# PH.net
KiCad netlist of a schematic drawn in Altium Designer
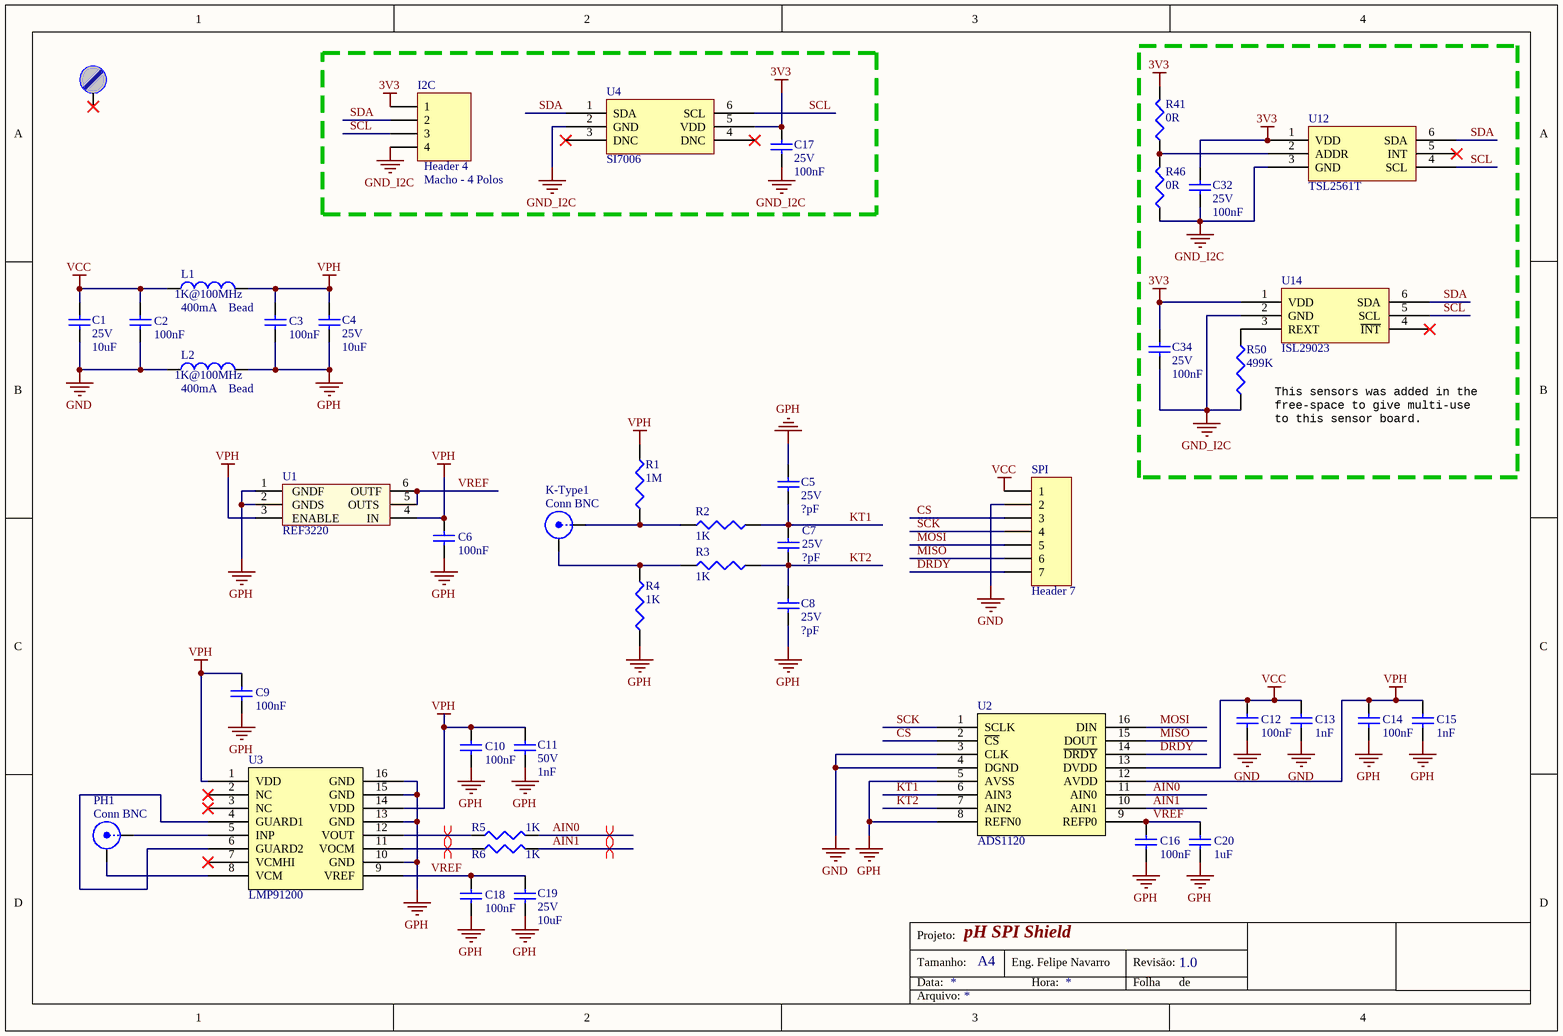
[diagram p0: PH.SchDoc]

(export (version "E")
  (design (tool "Eeschema 10.0.6"))
  (components
    (comp (ref "C1")
      (value "10uF")
      (footprint "CC0805")
      (description "Capacitor (Semiconductor SIM Model)")
      (fields (field (name "TENSÃO") "25V") (field (name "Comment") "Capacitor Cerâmico"))
      (libsource (lib "NavarroCAP") (part "Cap 10uF 25V 0805 X5R"))
    )
    (comp (ref "C2")
      (value "100nF")
      (footprint "CC0603")
      (description "Capacitor (Semiconductor SIM Model)")
      (fields (field (name "Comment") "Capacitor Cerâmico"))
      (libsource (lib "NavarroCAP") (part "Cap 100nF 25V 0603 X7R"))
    )
    (comp (ref "C3")
      (value "100nF")
      (footprint "CC0603")
      (description "Capacitor (Semiconductor SIM Model)")
      (fields (field (name "Comment") "Capacitor Cerâmico"))
      (libsource (lib "NavarroCAP") (part "Cap 100nF 25V 0603 X7R"))
    )
    (comp (ref "C4")
      (value "10uF")
      (footprint "CC0805")
      (description "Capacitor (Semiconductor SIM Model)")
      (fields (field (name "TENSÃO") "25V") (field (name "Comment") "Capacitor Cerâmico"))
      (libsource (lib "NavarroCAP") (part "Cap 10uF 25V 0805 X5R"))
    )
    (comp (ref "C5")
      (value "?pF")
      (footprint "CC0603")
      (description "Capacitor (Semiconductor SIM Model)")
      (fields (field (name "TENSÃO") "25V") (field (name "Comment") "Capacitor Cerâmico"))
      (libsource (lib "NavarroCAP") (part "Cap - $Val $V $Footprint $Classe_1"))
    )
    (comp (ref "C6")
      (value "100nF")
      (footprint "CC0603")
      (description "Capacitor (Semiconductor SIM Model)")
      (fields (field (name "Comment") "Capacitor Cerâmico"))
      (libsource (lib "NavarroCAP") (part "Cap 100nF 25V 0603 X7R"))
    )
    (comp (ref "C7")
      (value "?pF")
      (footprint "CC0603")
      (description "Capacitor (Semiconductor SIM Model)")
      (fields (field (name "TENSÃO") "25V") (field (name "Comment") "Capacitor Cerâmico"))
      (libsource (lib "NavarroCAP") (part "Cap - $Val $V $Footprint $Classe_1"))
    )
    (comp (ref "C8")
      (value "?pF")
      (footprint "CC0603")
      (description "Capacitor (Semiconductor SIM Model)")
      (fields (field (name "TENSÃO") "25V") (field (name "Comment") "Capacitor Cerâmico"))
      (libsource (lib "NavarroCAP") (part "Cap - $Val $V $Footprint $Classe_1"))
    )
    (comp (ref "C9")
      (value "100nF")
      (footprint "CC0603")
      (description "Capacitor (Semiconductor SIM Model)")
      (fields (field (name "Comment") "Capacitor Cerâmico"))
      (libsource (lib "NavarroCAP") (part "Cap 100nF 25V 0603 X7R"))
    )
    (comp (ref "C10")
      (value "100nF")
      (footprint "CC0603")
      (description "Capacitor (Semiconductor SIM Model)")
      (fields (field (name "Comment") "Capacitor Cerâmico"))
      (libsource (lib "NavarroCAP") (part "Cap 100nF 25V 0603 X7R"))
    )
    (comp (ref "C11")
      (value "1nF")
      (footprint "CC0603")
      (description "Capacitor (Semiconductor SIM Model)")
      (fields (field (name "TENSÃO") "50V") (field (name "Comment") "Capacitor Cerâmico"))
      (libsource (lib "NavarroCAP") (part "Cap 1nF 50V 0603 NP0"))
    )
    (comp (ref "C12")
      (value "100nF")
      (footprint "CC0603")
      (description "Capacitor (Semiconductor SIM Model)")
      (fields (field (name "Comment") "Capacitor Cerâmico"))
      (libsource (lib "NavarroCAP") (part "Cap 100nF 25V 0603 X7R"))
    )
    (comp (ref "C13")
      (value "1nF")
      (footprint "CC0603")
      (description "Capacitor (Semiconductor SIM Model)")
      (fields (field (name "Comment") "Capacitor Cerâmico"))
      (libsource (lib "NavarroCAP") (part "Cap 100nF 25V 0603 X7R"))
    )
    (comp (ref "C14")
      (value "100nF")
      (footprint "CC0603")
      (description "Capacitor (Semiconductor SIM Model)")
      (fields (field (name "Comment") "Capacitor Cerâmico"))
      (libsource (lib "NavarroCAP") (part "Cap 100nF 25V 0603 X7R"))
    )
    (comp (ref "C15")
      (value "1nF")
      (footprint "CC0603")
      (description "Capacitor (Semiconductor SIM Model)")
      (fields (field (name "Comment") "Capacitor Cerâmico"))
      (libsource (lib "NavarroCAP") (part "Cap 100nF 25V 0603 X7R"))
    )
    (comp (ref "C16")
      (value "100nF")
      (footprint "CC0603")
      (description "Capacitor (Semiconductor SIM Model)")
      (fields (field (name "Comment") "Capacitor Cerâmico"))
      (libsource (lib "NavarroCAP") (part "Cap 100nF 25V 0603 X7R"))
    )
    (comp (ref "C17")
      (value "100nF")
      (footprint "CC0603")
      (description "Capacitor (Semiconductor SIM Model)")
      (fields (field (name "TENSÃO") "25V") (field (name "Comment") "Capacitor Cerâmico"))
      (libsource (lib "NavarroCAP") (part "Cap 100nF 25V 0603 X7R"))
    )
    (comp (ref "C18")
      (value "100nF")
      (footprint "CC0603")
      (description "Capacitor (Semiconductor SIM Model)")
      (fields (field (name "Comment") "Capacitor Cerâmico"))
      (libsource (lib "NavarroCAP") (part "Cap 100nF 25V 0603 X7R"))
    )
    (comp (ref "C19")
      (value "10uF")
      (footprint "CC0805")
      (description "Capacitor (Semiconductor SIM Model)")
      (fields (field (name "TENSÃO") "25V") (field (name "Comment") "Capacitor Cerâmico"))
      (libsource (lib "NavarroCAP") (part "Cap 10uF 25V 0805 X5R"))
    )
    (comp (ref "C20")
      (value "1uF")
      (footprint "CC0603")
      (description "Capacitor (Semiconductor SIM Model)")
      (fields (field (name "Comment") "Capacitor Cerâmico"))
      (libsource (lib "NavarroCAP") (part "Cap 100nF 25V 0603 X7R"))
    )
    (comp (ref "C32")
      (value "100nF")
      (footprint "CC0603")
      (description "Capacitor (Semiconductor SIM Model)")
      (fields (field (name "TENSÃO") "25V") (field (name "Comment") "Capacitor Cerâmico"))
      (libsource (lib "NavarroCAP") (part "Cap 100nF 25V 0603 X7R"))
    )
    (comp (ref "C34")
      (value "100nF")
      (footprint "CC0603")
      (description "Capacitor (Semiconductor SIM Model)")
      (fields (field (name "TENSÃO") "25V") (field (name "Comment") "Capacitor Cerâmico"))
      (libsource (lib "NavarroCAP") (part "Cap 100nF 25V 0603 X7R"))
    )
    (comp (ref "I2C")
      (value "Header 4")
      (footprint "CONN HDR1X4")
      (description "Header, 4-Pin")
      (fields (field (name "ALTIUM_VALUE") "Macho - 4 Polos"))
      (libsource (lib "NavarroCON") (part "Header 4"))
    )
    (comp (ref "K-Type1")
      (value "Conn BNC")
      (footprint "CONN BNC-JACK")
      (description "Conector BNC")
      (libsource (lib "NavarroCON") (part "Conn BNC"))
    )
    (comp (ref "L1")
      (value "Bead")
      (footprint "CC0603")
      (fields (field (name "CORRENTE") "400mA") (field (name "ALTIUM_VALUE") "1K@100MHz"))
      (libsource (lib "NavarroIND") (part "Bd 1K@100MHz 0603 400mA"))
    )
    (comp (ref "L2")
      (value "Bead")
      (footprint "CC0603")
      (fields (field (name "CORRENTE") "400mA") (field (name "ALTIUM_VALUE") "1K@100MHz"))
      (libsource (lib "NavarroIND") (part "Bd 1K@100MHz 0603 400mA"))
    )
    (comp (ref "M2")
      (value "Furo de Fixação")
      (footprint "Furo_M3")
      (description "Furo para parafuso")
      (libsource (lib "Tecnoclade") (part "Parafuso"))
    )
    (comp (ref "PH1")
      (value "Conn BNC")
      (footprint "CONN BNC-JACK")
      (description "Conector BNC")
      (libsource (lib "NavarroCON") (part "Conn BNC"))
    )
    (comp (ref "R1")
      (value "1M")
      (footprint "CC0603")
      (description "Resistor")
      (libsource (lib "NavarroRES") (part "Res - $Val $% $Footprint $Pot"))
    )
    (comp (ref "R2")
      (value "1K")
      (footprint "CC0603")
      (description "Resistor")
      (libsource (lib "NavarroRES") (part "Res - $Val $% $Footprint $Pot"))
    )
    (comp (ref "R3")
      (value "1K")
      (footprint "CC0603")
      (description "Resistor")
      (libsource (lib "NavarroRES") (part "Res - $Val $% $Footprint $Pot"))
    )
    (comp (ref "R4")
      (value "1K")
      (footprint "CC0603")
      (description "Resistor")
      (libsource (lib "NavarroRES") (part "Res - $Val $% $Footprint $Pot"))
    )
    (comp (ref "R5")
      (value "1K")
      (footprint "CC0603")
      (description "Resistor")
      (libsource (lib "NavarroRES") (part "Res 1K 1% 0603 1/10W"))
    )
    (comp (ref "R6")
      (value "1K")
      (footprint "CC0603")
      (description "Resistor")
      (libsource (lib "NavarroRES") (part "Res 1K 1% 0603 1/10W"))
    )
    (comp (ref "R41")
      (value "0R")
      (footprint "CC0603")
      (description "Resistor")
      (libsource (lib "NavarroRES") (part "Res 0R 0603 1/10W"))
    )
    (comp (ref "R46")
      (value "0R")
      (footprint "CC0603")
      (description "Resistor")
      (libsource (lib "NavarroRES") (part "Res 0R 0603 1/10W"))
    )
    (comp (ref "R50")
      (value "499K")
      (footprint "CC0603")
      (description "Resistor")
      (libsource (lib "NavarroRES") (part "Res 499K 1% 0603 1/10W"))
    )
    (comp (ref "SPI")
      (value "Header 7")
      (footprint "CONN HDR1X7")
      (description "Header, 7-Pin")
      (libsource (lib "NavarroCON") (part "Header 7"))
    )
    (comp (ref "U1")
      (value "REF3220")
      (footprint "SOT-23-6N")
      (description "2.048v Precision Voltage Reference")
      (libsource (lib "Navarro") (part "REF3220"))
    )
    (comp (ref "U2")
      (value "ADS1120")
      (footprint "TSSOP-16N")
      (description "ADS1120 Low-Power, Low-Noise, 16-Bit ADC for Small-Signal Sensors")
      (libsource (lib "Navarro") (part "ADS1120IPWR"))
    )
    (comp (ref "U3")
      (value "LMP91200")
      (footprint "TSSOP-16N")
      (description "AFE for Low-Power Chemical-Sensing Applications")
      (libsource (lib "Navarro") (part "LMP91200"))
    )
    (comp (ref "U4")
      (value "SI7006")
      (footprint "QFN3x3-6P")
      (description "SI7021-A20-GM1")
      (libsource (lib "Navarro") (part "SI7006"))
    )
    (comp (ref "U12")
      (value "TSL2561T")
      (footprint "TSL2561-TMB6")
      (description "Lux Meter")
      (libsource (lib "Navarro") (part "TSL2561T"))
    )
    (comp (ref "U14")
      (value "ISL29023")
      (footprint "QFN2x2-6")
      (description "Lux Meter")
      (libsource (lib "Navarro") (part "ISL29023"))
    )
  )
  (nets
    (net (code "1") (name "/AIN0") (class "Default")
      (node (ref "R5") (pin "2") (pinfunction "2_2") (pintype "passive"))
      (node (ref "U2") (pin "11") (pinfunction "AIN0_11") (pintype "passive"))
    )
    (net (code "2") (name "/AIN1") (class "Default")
      (node (ref "R6") (pin "2") (pinfunction "2_2") (pintype "passive"))
      (node (ref "U2") (pin "10") (pinfunction "AIN1_10") (pintype "passive"))
    )
    (net (code "3") (name "/CS") (class "Default")
      (node (ref "SPI") (pin "3") (pinfunction "3_3") (pintype "passive"))
      (node (ref "U2") (pin "2") (pinfunction "~{CS}_2") (pintype "passive"))
    )
    (net (code "4") (name "/DRDY") (class "Default")
      (node (ref "SPI") (pin "7") (pinfunction "7_7") (pintype "passive"))
      (node (ref "U2") (pin "14") (pinfunction "~{DRDY}_14") (pintype "passive"))
    )
    (net (code "5") (name "/KT1") (class "Default")
      (node (ref "C5") (pin "1") (pinfunction "1_1") (pintype "passive"))
      (node (ref "C7") (pin "2") (pinfunction "2_2") (pintype "passive"))
      (node (ref "R2") (pin "1") (pinfunction "1_1") (pintype "passive"))
      (node (ref "U2") (pin "6") (pinfunction "AIN3_6") (pintype "passive"))
    )
    (net (code "6") (name "/KT2") (class "Default")
      (node (ref "C7") (pin "1") (pinfunction "1_1") (pintype "passive"))
      (node (ref "C8") (pin "2") (pinfunction "2_2") (pintype "passive"))
      (node (ref "R3") (pin "2") (pinfunction "2_2") (pintype "passive"))
      (node (ref "U2") (pin "7") (pinfunction "AIN2_7") (pintype "passive"))
    )
    (net (code "7") (name "/MISO") (class "Default")
      (node (ref "SPI") (pin "6") (pinfunction "6_6") (pintype "passive"))
      (node (ref "U2") (pin "15") (pinfunction "DOUT_15") (pintype "passive"))
    )
    (net (code "8") (name "/MOSI") (class "Default")
      (node (ref "SPI") (pin "5") (pinfunction "5_5") (pintype "passive"))
      (node (ref "U2") (pin "16") (pinfunction "DIN_16") (pintype "passive"))
    )
    (net (code "9") (name "/SCK") (class "Default")
      (node (ref "SPI") (pin "4") (pinfunction "4_4") (pintype "passive"))
      (node (ref "U2") (pin "1") (pinfunction "SCLK_1") (pintype "passive"))
    )
    (net (code "10") (name "/SCL") (class "Default")
      (node (ref "I2C") (pin "3") (pinfunction "3_3") (pintype "passive"))
      (node (ref "U12") (pin "4") (pinfunction "SCL_4") (pintype "passive"))
      (node (ref "U14") (pin "5") (pinfunction "SCL_5") (pintype "power_in"))
      (node (ref "U4") (pin "6") (pinfunction "SCL_6") (pintype "passive"))
    )
    (net (code "11") (name "/SDA") (class "Default")
      (node (ref "I2C") (pin "2") (pinfunction "2_2") (pintype "passive"))
      (node (ref "U12") (pin "6") (pinfunction "SDA_6") (pintype "passive"))
      (node (ref "U14") (pin "6") (pinfunction "SDA_6") (pintype "passive"))
      (node (ref "U4") (pin "1") (pinfunction "SDA_1") (pintype "passive"))
    )
    (net (code "12") (name "/VREF") (class "Default")
      (node (ref "C16") (pin "2") (pinfunction "2_2") (pintype "passive"))
      (node (ref "C18") (pin "2") (pinfunction "2_2") (pintype "passive"))
      (node (ref "C19") (pin "2") (pinfunction "2_2") (pintype "passive"))
      (node (ref "C20") (pin "2") (pinfunction "2_2") (pintype "passive"))
      (node (ref "U1") (pin "5") (pinfunction "OUTS_5") (pintype "power_in"))
      (node (ref "U1") (pin "6") (pinfunction "OUTF_6") (pintype "power_in"))
      (node (ref "U2") (pin "9") (pinfunction "REFP0_9") (pintype "passive"))
      (node (ref "U3") (pin "9") (pinfunction "VREF_9") (pintype "passive"))
    )
    (net (code "13") (name "3V3") (class "Default")
      (node (ref "C17") (pin "2") (pinfunction "2_2") (pintype "passive"))
      (node (ref "C32") (pin "2") (pinfunction "2_2") (pintype "passive"))
      (node (ref "C34") (pin "2") (pinfunction "2_2") (pintype "passive"))
      (node (ref "I2C") (pin "1") (pinfunction "1_1") (pintype "passive"))
      (node (ref "R41") (pin "2") (pinfunction "2_2") (pintype "passive"))
      (node (ref "U12") (pin "1") (pinfunction "VDD_1") (pintype "passive"))
      (node (ref "U14") (pin "1") (pinfunction "VDD_1") (pintype "passive"))
      (node (ref "U4") (pin "5") (pinfunction "VDD_5") (pintype "power_in"))
    )
    (net (code "14") (name "GND") (class "Default")
      (node (ref "C1") (pin "1") (pinfunction "1_1") (pintype "passive"))
      (node (ref "C12") (pin "1") (pinfunction "1_1") (pintype "passive"))
      (node (ref "C13") (pin "1") (pinfunction "1_1") (pintype "passive"))
      (node (ref "C2") (pin "1") (pinfunction "1_1") (pintype "passive"))
      (node (ref "L2") (pin "1") (pinfunction "1_1") (pintype "passive"))
      (node (ref "SPI") (pin "2") (pinfunction "2_2") (pintype "passive"))
      (node (ref "U2") (pin "3") (pinfunction "CLK_3") (pintype "passive"))
      (node (ref "U2") (pin "4") (pinfunction "DGND_4") (pintype "power_in"))
    )
    (net (code "15") (name "GND_I2C") (class "Default")
      (node (ref "C17") (pin "1") (pinfunction "1_1") (pintype "passive"))
      (node (ref "C32") (pin "1") (pinfunction "1_1") (pintype "passive"))
      (node (ref "C34") (pin "1") (pinfunction "1_1") (pintype "passive"))
      (node (ref "I2C") (pin "4") (pinfunction "4_4") (pintype "passive"))
      (node (ref "R46") (pin "1") (pinfunction "1_1") (pintype "passive"))
      (node (ref "R50") (pin "1") (pinfunction "1_1") (pintype "passive"))
      (node (ref "U12") (pin "3") (pinfunction "GND_3") (pintype "passive"))
      (node (ref "U14") (pin "2") (pinfunction "GND_2") (pintype "passive"))
      (node (ref "U4") (pin "2") (pinfunction "GND_2") (pintype "passive"))
    )
    (net (code "16") (name "GPH") (class "Default")
      (node (ref "C10") (pin "1") (pinfunction "1_1") (pintype "passive"))
      (node (ref "C11") (pin "1") (pinfunction "1_1") (pintype "passive"))
      (node (ref "C14") (pin "1") (pinfunction "1_1") (pintype "passive"))
      (node (ref "C15") (pin "1") (pinfunction "1_1") (pintype "passive"))
      (node (ref "C16") (pin "1") (pinfunction "1_1") (pintype "passive"))
      (node (ref "C18") (pin "1") (pinfunction "1_1") (pintype "passive"))
      (node (ref "C19") (pin "1") (pinfunction "1_1") (pintype "passive"))
      (node (ref "C20") (pin "1") (pinfunction "1_1") (pintype "passive"))
      (node (ref "C3") (pin "1") (pinfunction "1_1") (pintype "passive"))
      (node (ref "C4") (pin "1") (pinfunction "1_1") (pintype "passive"))
      (node (ref "C5") (pin "2") (pinfunction "2_2") (pintype "passive"))
      (node (ref "C6") (pin "1") (pinfunction "1_1") (pintype "passive"))
      (node (ref "C8") (pin "1") (pinfunction "1_1") (pintype "passive"))
      (node (ref "C9") (pin "1") (pinfunction "1_1") (pintype "passive"))
      (node (ref "L2") (pin "2") (pinfunction "2_2") (pintype "passive"))
      (node (ref "R4") (pin "2") (pinfunction "2_2") (pintype "passive"))
      (node (ref "U1") (pin "1") (pinfunction "GNDF_1") (pintype "power_in"))
      (node (ref "U1") (pin "2") (pinfunction "GNDS_2") (pintype "power_in"))
      (node (ref "U2") (pin "5") (pinfunction "AVSS_5") (pintype "power_in"))
      (node (ref "U2") (pin "8") (pinfunction "REFN0_8") (pintype "passive"))
      (node (ref "U3") (pin "10") (pinfunction "GND_10") (pintype "passive"))
      (node (ref "U3") (pin "13") (pinfunction "GND_13") (pintype "passive"))
      (node (ref "U3") (pin "15") (pinfunction "GND_15") (pintype "passive"))
      (node (ref "U3") (pin "16") (pinfunction "GND_16") (pintype "passive"))
    )
    (net (code "17") (name "Net-(K-Type1-X)") (class "Default")
      (node (ref "K-Type1") (pin "1") (pinfunction "X_1") (pintype "passive"))
      (node (ref "R1") (pin "1") (pinfunction "1_1") (pintype "passive"))
      (node (ref "R2") (pin "2") (pinfunction "2_2") (pintype "passive"))
    )
    (net (code "18") (name "Net-(K-Type1-Y)") (class "Default")
      (node (ref "K-Type1") (pin "2") (pinfunction "Y_2") (pintype "passive"))
      (node (ref "R3") (pin "1") (pinfunction "1_1") (pintype "passive"))
      (node (ref "R4") (pin "1") (pinfunction "1_1") (pintype "passive"))
    )
    (net (code "19") (name "Net-(PH1-X)") (class "Default")
      (node (ref "PH1") (pin "1") (pinfunction "X_1") (pintype "passive"))
      (node (ref "U3") (pin "5") (pinfunction "INP_5") (pintype "passive"))
    )
    (net (code "20") (name "Net-(PH1-Y)") (class "Default")
      (node (ref "PH1") (pin "2") (pinfunction "Y_2") (pintype "passive"))
      (node (ref "U3") (pin "8") (pinfunction "VCM_8") (pintype "passive"))
    )
    (net (code "21") (name "Net-(U3-GUARD1)") (class "Default")
      (node (ref "U3") (pin "4") (pinfunction "GUARD1_4") (pintype "passive"))
      (node (ref "U3") (pin "6") (pinfunction "GUARD2_6") (pintype "passive"))
    )
    (net (code "22") (name "Net-(U3-VOCM)") (class "Default")
      (node (ref "R6") (pin "1") (pinfunction "1_1") (pintype "passive"))
      (node (ref "U3") (pin "11") (pinfunction "VOCM_11") (pintype "passive"))
    )
    (net (code "23") (name "Net-(U3-VOUT)") (class "Default")
      (node (ref "R5") (pin "1") (pinfunction "1_1") (pintype "passive"))
      (node (ref "U3") (pin "12") (pinfunction "VOUT_12") (pintype "passive"))
    )
    (net (code "24") (name "Net-(U12-ADDR)") (class "Default")
      (node (ref "R41") (pin "1") (pinfunction "1_1") (pintype "passive"))
      (node (ref "R46") (pin "2") (pinfunction "2_2") (pintype "passive"))
      (node (ref "U12") (pin "2") (pinfunction "ADDR_2") (pintype "passive"))
    )
    (net (code "25") (name "Net-(U14-REXT)") (class "Default")
      (node (ref "R50") (pin "2") (pinfunction "2_2") (pintype "passive"))
      (node (ref "U14") (pin "3") (pinfunction "REXT_3") (pintype "passive"))
    )
    (net (code "26") (name "VCC") (class "Default")
      (node (ref "C1") (pin "2") (pinfunction "2_2") (pintype "passive"))
      (node (ref "C12") (pin "2") (pinfunction "2_2") (pintype "passive"))
      (node (ref "C13") (pin "2") (pinfunction "2_2") (pintype "passive"))
      (node (ref "C2") (pin "2") (pinfunction "2_2") (pintype "passive"))
      (node (ref "L1") (pin "1") (pinfunction "1_1") (pintype "passive"))
      (node (ref "SPI") (pin "1") (pinfunction "1_1") (pintype "passive"))
      (node (ref "U2") (pin "13") (pinfunction "DVDD_13") (pintype "power_in"))
    )
    (net (code "27") (name "VPH") (class "Default")
      (node (ref "C10") (pin "2") (pinfunction "2_2") (pintype "passive"))
      (node (ref "C11") (pin "2") (pinfunction "2_2") (pintype "passive"))
      (node (ref "C14") (pin "2") (pinfunction "2_2") (pintype "passive"))
      (node (ref "C15") (pin "2") (pinfunction "2_2") (pintype "passive"))
      (node (ref "C3") (pin "2") (pinfunction "2_2") (pintype "passive"))
      (node (ref "C4") (pin "2") (pinfunction "2_2") (pintype "passive"))
      (node (ref "C6") (pin "2") (pinfunction "2_2") (pintype "passive"))
      (node (ref "C9") (pin "2") (pinfunction "2_2") (pintype "passive"))
      (node (ref "L1") (pin "2") (pinfunction "2_2") (pintype "passive"))
      (node (ref "R1") (pin "2") (pinfunction "2_2") (pintype "passive"))
      (node (ref "U1") (pin "3") (pinfunction "ENABLE_3") (pintype "passive"))
      (node (ref "U1") (pin "4") (pinfunction "IN_4") (pintype "passive"))
      (node (ref "U2") (pin "12") (pinfunction "AVDD_12") (pintype "power_in"))
      (node (ref "U3") (pin "1") (pinfunction "VDD_1") (pintype "passive"))
      (node (ref "U3") (pin "14") (pinfunction "VDD_14") (pintype "passive"))
    )
    (net (code "28") (name "unconnected-(M2-PadX)") (class "Default")
      (node (ref "M2") (pin "X") (pinfunction "X_X") (pintype "passive+no_connect"))
    )
    (net (code "29") (name "unconnected-(U3-NC-Pad2)") (class "Default")
      (node (ref "U3") (pin "2") (pinfunction "NC_2") (pintype "passive+no_connect"))
    )
    (net (code "30") (name "unconnected-(U3-NC-Pad3)") (class "Default")
      (node (ref "U3") (pin "3") (pinfunction "NC_3") (pintype "passive+no_connect"))
    )
    (net (code "31") (name "unconnected-(U3-VCMHI-Pad7)") (class "Default")
      (node (ref "U3") (pin "7") (pinfunction "VCMHI_7") (pintype "passive+no_connect"))
    )
    (net (code "32") (name "unconnected-(U4-DNC-Pad3)") (class "Default")
      (node (ref "U4") (pin "3") (pinfunction "DNC_3") (pintype "passive+no_connect"))
    )
    (net (code "33") (name "unconnected-(U4-DNC-Pad4)") (class "Default")
      (node (ref "U4") (pin "4") (pinfunction "DNC_4") (pintype "passive+no_connect"))
    )
    (net (code "34") (name "unconnected-(U12-INT-Pad5)") (class "Default")
      (node (ref "U12") (pin "5") (pinfunction "INT_5") (pintype "power_in+no_connect"))
    )
    (net (code "35") (name "unconnected-(U14-~{INT}-Pad4)") (class "Default")
      (node (ref "U14") (pin "4") (pinfunction "~{INT}_4") (pintype "passive+no_connect"))
    )
  )
)
